# iceWerx_Carrier.net
KiCad netlist of a schematic drawn in EAGLE
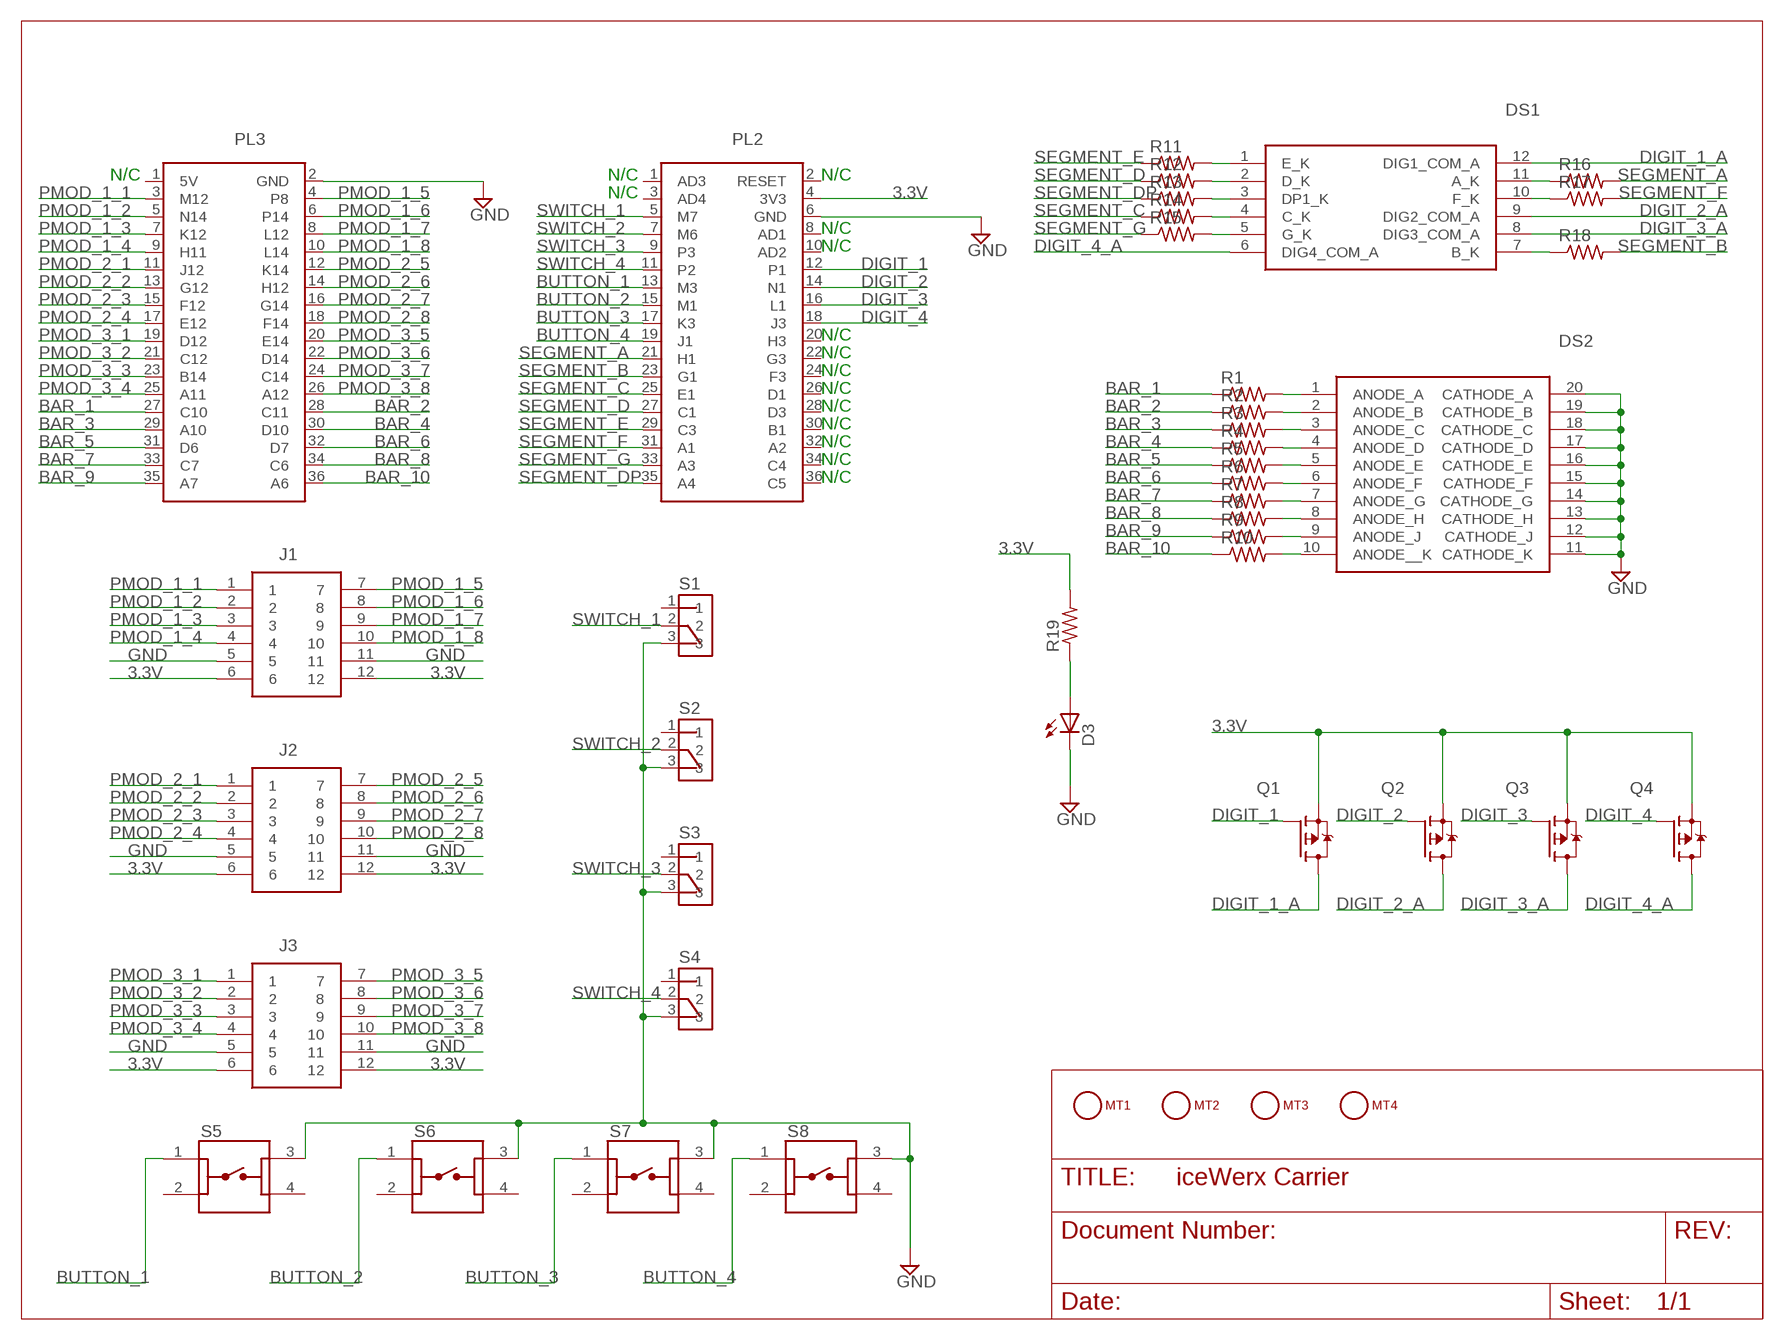
[diagram p0: schematic, sheet 1]

(export (version "E")
  (design (tool "Eeschema 10.0.6"))
  (components
    (comp (ref "D3")
      (value "LED5MM")
      (footprint "eagle-import:LED5MM")
      (libsource (lib "eagle-import") (part "LED5MM"))
    )
    (comp (ref "DS1")
      (value "LDQ-M282RI")
      (footprint "eagle-import:LDQM282RI")
      (fields (field (name "MOUSER_PART_NUMBER") "696-LDQ-M282RI"))
      (libsource (lib "eagle-import") (part "LDQ-M282RI"))
    )
    (comp (ref "DS2")
      (value "LTA-1000G")
      (footprint "eagle-import:DIPS762W50P254L2527H825Q20N")
      (fields (field (name "MOUSER_PART_NUMBER") "859-LTA-1000G"))
      (libsource (lib "eagle-import") (part "LTA-1000G"))
    )
    (comp (ref "J1")
      (value "PMOD-SOCKET-FOR-HOST-BOARD")
      (footprint "eagle-import:PMOD-SOCKET-FOR-HOST-BOARD")
      (libsource (lib "eagle-import") (part "PMOD-SOCKET-FOR-HOST-BOARD"))
    )
    (comp (ref "J2")
      (value "PMOD-SOCKET-FOR-HOST-BOARD")
      (footprint "eagle-import:PMOD-SOCKET-FOR-HOST-BOARD")
      (libsource (lib "eagle-import") (part "PMOD-SOCKET-FOR-HOST-BOARD"))
    )
    (comp (ref "J3")
      (value "PMOD-SOCKET-FOR-HOST-BOARD")
      (footprint "eagle-import:PMOD-SOCKET-FOR-HOST-BOARD")
      (libsource (lib "eagle-import") (part "PMOD-SOCKET-FOR-HOST-BOARD"))
    )
    (comp (ref "MT1")
      (value "MOUNTING_HOLE-125_250_ROUND")
      (footprint "eagle-import:MT_125_250")
      (libsource (lib "eagle-import") (part "MOUNTING_HOLE-125_250_ROUND"))
    )
    (comp (ref "MT2")
      (value "MOUNTING_HOLE-125_250_ROUND")
      (footprint "eagle-import:MT_125_250")
      (libsource (lib "eagle-import") (part "MOUNTING_HOLE-125_250_ROUND"))
    )
    (comp (ref "MT3")
      (value "MOUNTING_HOLE-125_250_ROUND")
      (footprint "eagle-import:MT_125_250")
      (libsource (lib "eagle-import") (part "MOUNTING_HOLE-125_250_ROUND"))
    )
    (comp (ref "MT4")
      (value "MOUNTING_HOLE-125_250_ROUND")
      (footprint "eagle-import:MT_125_250")
      (libsource (lib "eagle-import") (part "MOUNTING_HOLE-125_250_ROUND"))
    )
    (comp (ref "PL2")
      (value "ICEWERX-PL2")
      (footprint "eagle-import:TE_4-1734506-1")
      (libsource (lib "eagle-import") (part "ICEWERX-PL2"))
    )
    (comp (ref "PL3")
      (value "ICEWERX-PL3")
      (footprint "eagle-import:TE_4-1734506-1")
      (libsource (lib "eagle-import") (part "ICEWERX-PL3"))
    )
    (comp (ref "Q1")
      (value "NX2301P")
      (footprint "eagle-import:SOT95P230X110-3N")
      (fields (field (name "MANUFACTURER") "Nexperia"))
      (libsource (lib "eagle-import") (part "NX2301P"))
    )
    (comp (ref "Q2")
      (value "NX2301P")
      (footprint "eagle-import:SOT95P230X110-3N")
      (fields (field (name "MANUFACTURER") "Nexperia"))
      (libsource (lib "eagle-import") (part "NX2301P"))
    )
    (comp (ref "Q3")
      (value "NX2301P")
      (footprint "eagle-import:SOT95P230X110-3N")
      (fields (field (name "MANUFACTURER") "Nexperia"))
      (libsource (lib "eagle-import") (part "NX2301P"))
    )
    (comp (ref "Q4")
      (value "NX2301P")
      (footprint "eagle-import:SOT95P230X110-3N")
      (fields (field (name "MANUFACTURER") "Nexperia"))
      (libsource (lib "eagle-import") (part "NX2301P"))
    )
    (comp (ref "R1")
      (value "R-US_0204/5")
      (footprint "eagle-import:0204_5")
      (libsource (lib "eagle-import") (part "R-US_0204/5"))
    )
    (comp (ref "R2")
      (value "R-US_0204/5")
      (footprint "eagle-import:0204_5")
      (libsource (lib "eagle-import") (part "R-US_0204/5"))
    )
    (comp (ref "R3")
      (value "R-US_0204/5")
      (footprint "eagle-import:0204_5")
      (libsource (lib "eagle-import") (part "R-US_0204/5"))
    )
    (comp (ref "R4")
      (value "R-US_0204/5")
      (footprint "eagle-import:0204_5")
      (libsource (lib "eagle-import") (part "R-US_0204/5"))
    )
    (comp (ref "R5")
      (value "R-US_0204/5")
      (footprint "eagle-import:0204_5")
      (libsource (lib "eagle-import") (part "R-US_0204/5"))
    )
    (comp (ref "R6")
      (value "R-US_0204/5")
      (footprint "eagle-import:0204_5")
      (libsource (lib "eagle-import") (part "R-US_0204/5"))
    )
    (comp (ref "R7")
      (value "R-US_0204/5")
      (footprint "eagle-import:0204_5")
      (libsource (lib "eagle-import") (part "R-US_0204/5"))
    )
    (comp (ref "R8")
      (value "R-US_0204/5")
      (footprint "eagle-import:0204_5")
      (libsource (lib "eagle-import") (part "R-US_0204/5"))
    )
    (comp (ref "R9")
      (value "R-US_0204/5")
      (footprint "eagle-import:0204_5")
      (libsource (lib "eagle-import") (part "R-US_0204/5"))
    )
    (comp (ref "R10")
      (value "R-US_0204/5")
      (footprint "eagle-import:0204_5")
      (libsource (lib "eagle-import") (part "R-US_0204/5"))
    )
    (comp (ref "R11")
      (value "R-US_0204/5")
      (footprint "eagle-import:0204_5")
      (libsource (lib "eagle-import") (part "R-US_0204/5"))
    )
    (comp (ref "R12")
      (value "R-US_0204/5")
      (footprint "eagle-import:0204_5")
      (libsource (lib "eagle-import") (part "R-US_0204/5"))
    )
    (comp (ref "R13")
      (value "R-US_0204/5")
      (footprint "eagle-import:0204_5")
      (libsource (lib "eagle-import") (part "R-US_0204/5"))
    )
    (comp (ref "R14")
      (value "R-US_0204/5")
      (footprint "eagle-import:0204_5")
      (libsource (lib "eagle-import") (part "R-US_0204/5"))
    )
    (comp (ref "R15")
      (value "R-US_0204/5")
      (footprint "eagle-import:0204_5")
      (libsource (lib "eagle-import") (part "R-US_0204/5"))
    )
    (comp (ref "R16")
      (value "R-US_0204/5")
      (footprint "eagle-import:0204_5")
      (libsource (lib "eagle-import") (part "R-US_0204/5"))
    )
    (comp (ref "R17")
      (value "R-US_0204/5")
      (footprint "eagle-import:0204_5")
      (libsource (lib "eagle-import") (part "R-US_0204/5"))
    )
    (comp (ref "R18")
      (value "R-US_0204/5")
      (footprint "eagle-import:0204_5")
      (libsource (lib "eagle-import") (part "R-US_0204/5"))
    )
    (comp (ref "R19")
      (value "R-US_0204/5")
      (footprint "eagle-import:0204_5")
      (libsource (lib "eagle-import") (part "R-US_0204/5"))
    )
    (comp (ref "S1")
      (value "OS102011MS2QN1")
      (footprint "eagle-import:SW_OS102011MS2QN1")
      (fields (field (name "MANUFACTURER") "C&K"))
      (libsource (lib "eagle-import") (part "OS102011MS2QN1"))
    )
    (comp (ref "S2")
      (value "OS102011MS2QN1")
      (footprint "eagle-import:SW_OS102011MS2QN1")
      (fields (field (name "MANUFACTURER") "C&K"))
      (libsource (lib "eagle-import") (part "OS102011MS2QN1"))
    )
    (comp (ref "S3")
      (value "OS102011MS2QN1")
      (footprint "eagle-import:SW_OS102011MS2QN1")
      (fields (field (name "MANUFACTURER") "C&K"))
      (libsource (lib "eagle-import") (part "OS102011MS2QN1"))
    )
    (comp (ref "S4")
      (value "OS102011MS2QN1")
      (footprint "eagle-import:SW_OS102011MS2QN1")
      (fields (field (name "MANUFACTURER") "C&K"))
      (libsource (lib "eagle-import") (part "OS102011MS2QN1"))
    )
    (comp (ref "S5")
      (value "1825910-7")
      (footprint "eagle-import:SW_1825910-7")
      (fields (field (name "MANUFACTURER") "TE Connectivity"))
      (libsource (lib "eagle-import") (part "1825910-7"))
    )
    (comp (ref "S6")
      (value "1825910-7")
      (footprint "eagle-import:SW_1825910-7")
      (fields (field (name "MANUFACTURER") "TE Connectivity"))
      (libsource (lib "eagle-import") (part "1825910-7"))
    )
    (comp (ref "S7")
      (value "1825910-7")
      (footprint "eagle-import:SW_1825910-7")
      (fields (field (name "MANUFACTURER") "TE Connectivity"))
      (libsource (lib "eagle-import") (part "1825910-7"))
    )
    (comp (ref "S8")
      (value "1825910-7")
      (footprint "eagle-import:SW_1825910-7")
      (fields (field (name "MANUFACTURER") "TE Connectivity"))
      (libsource (lib "eagle-import") (part "1825910-7"))
    )
  )
  (nets
    (net (code "1") (name "/3.3V") (class "Default")
      (node (ref "J1") (pin "12") (pinfunction "12_12") (pintype "bidirectional"))
      (node (ref "J1") (pin "6") (pinfunction "6_6") (pintype "bidirectional"))
      (node (ref "J2") (pin "12") (pinfunction "12_12") (pintype "bidirectional"))
      (node (ref "J2") (pin "6") (pinfunction "6_6") (pintype "bidirectional"))
      (node (ref "J3") (pin "12") (pinfunction "12_12") (pintype "bidirectional"))
      (node (ref "J3") (pin "6") (pinfunction "6_6") (pintype "bidirectional"))
      (node (ref "PL2") (pin "4") (pinfunction "3V3_4") (pintype "bidirectional"))
      (node (ref "Q1") (pin "2") (pinfunction "S_2") (pintype "passive"))
      (node (ref "Q2") (pin "2") (pinfunction "S_2") (pintype "passive"))
      (node (ref "Q3") (pin "2") (pinfunction "S_2") (pintype "passive"))
      (node (ref "Q4") (pin "2") (pinfunction "S_2") (pintype "passive"))
      (node (ref "R19") (pin "2") (pinfunction "2_2") (pintype "passive"))
    )
    (net (code "2") (name "/BAR_1") (class "Default")
      (node (ref "PL3") (pin "27") (pinfunction "C10_27") (pintype "bidirectional"))
      (node (ref "R1") (pin "1") (pinfunction "1_1") (pintype "passive"))
    )
    (net (code "3") (name "/BAR_2") (class "Default")
      (node (ref "PL3") (pin "28") (pinfunction "C11_28") (pintype "bidirectional"))
      (node (ref "R2") (pin "1") (pinfunction "1_1") (pintype "passive"))
    )
    (net (code "4") (name "/BAR_3") (class "Default")
      (node (ref "PL3") (pin "29") (pinfunction "A10_29") (pintype "bidirectional"))
      (node (ref "R3") (pin "1") (pinfunction "1_1") (pintype "passive"))
    )
    (net (code "5") (name "/BAR_4") (class "Default")
      (node (ref "PL3") (pin "30") (pinfunction "D10_30") (pintype "bidirectional"))
      (node (ref "R4") (pin "1") (pinfunction "1_1") (pintype "passive"))
    )
    (net (code "6") (name "/BAR_5") (class "Default")
      (node (ref "PL3") (pin "31") (pinfunction "D6_31") (pintype "bidirectional"))
      (node (ref "R5") (pin "1") (pinfunction "1_1") (pintype "passive"))
    )
    (net (code "7") (name "/BAR_6") (class "Default")
      (node (ref "PL3") (pin "32") (pinfunction "D7_32") (pintype "bidirectional"))
      (node (ref "R6") (pin "1") (pinfunction "1_1") (pintype "passive"))
    )
    (net (code "8") (name "/BAR_7") (class "Default")
      (node (ref "PL3") (pin "33") (pinfunction "C7_33") (pintype "bidirectional"))
      (node (ref "R7") (pin "1") (pinfunction "1_1") (pintype "passive"))
    )
    (net (code "9") (name "/BAR_8") (class "Default")
      (node (ref "PL3") (pin "34") (pinfunction "C6_34") (pintype "bidirectional"))
      (node (ref "R8") (pin "1") (pinfunction "1_1") (pintype "passive"))
    )
    (net (code "10") (name "/BAR_9") (class "Default")
      (node (ref "PL3") (pin "35") (pinfunction "A7_35") (pintype "bidirectional"))
      (node (ref "R9") (pin "1") (pinfunction "1_1") (pintype "passive"))
    )
    (net (code "11") (name "/BAR_10") (class "Default")
      (node (ref "PL3") (pin "36") (pinfunction "A6_36") (pintype "bidirectional"))
      (node (ref "R10") (pin "1") (pinfunction "1_1") (pintype "passive"))
    )
    (net (code "12") (name "/BUTTON_1") (class "Default")
      (node (ref "PL2") (pin "13") (pinfunction "M3_13") (pintype "bidirectional"))
      (node (ref "S5") (pin "1") (pinfunction "1_1") (pintype "passive"))
    )
    (net (code "13") (name "/BUTTON_2") (class "Default")
      (node (ref "PL2") (pin "15") (pinfunction "M1_15") (pintype "bidirectional"))
      (node (ref "S6") (pin "1") (pinfunction "1_1") (pintype "passive"))
    )
    (net (code "14") (name "/BUTTON_3") (class "Default")
      (node (ref "PL2") (pin "17") (pinfunction "K3_17") (pintype "bidirectional"))
      (node (ref "S7") (pin "1") (pinfunction "1_1") (pintype "passive"))
    )
    (net (code "15") (name "/BUTTON_4") (class "Default")
      (node (ref "PL2") (pin "19") (pinfunction "J1_19") (pintype "bidirectional"))
      (node (ref "S8") (pin "1") (pinfunction "1_1") (pintype "passive"))
    )
    (net (code "16") (name "/DIGIT_1") (class "Default")
      (node (ref "PL2") (pin "12") (pinfunction "P1_12") (pintype "bidirectional"))
      (node (ref "Q1") (pin "1") (pinfunction "G_1") (pintype "passive"))
    )
    (net (code "17") (name "/DIGIT_1_A") (class "Default")
      (node (ref "DS1") (pin "12") (pinfunction "DIG1_COM_A_12") (pintype "bidirectional"))
      (node (ref "Q1") (pin "3") (pinfunction "D_3") (pintype "passive"))
    )
    (net (code "18") (name "/DIGIT_2") (class "Default")
      (node (ref "PL2") (pin "14") (pinfunction "N1_14") (pintype "bidirectional"))
      (node (ref "Q2") (pin "1") (pinfunction "G_1") (pintype "passive"))
    )
    (net (code "19") (name "/DIGIT_2_A") (class "Default")
      (node (ref "DS1") (pin "9") (pinfunction "DIG2_COM_A_9") (pintype "bidirectional"))
      (node (ref "Q2") (pin "3") (pinfunction "D_3") (pintype "passive"))
    )
    (net (code "20") (name "/DIGIT_3") (class "Default")
      (node (ref "PL2") (pin "16") (pinfunction "L1_16") (pintype "bidirectional"))
      (node (ref "Q3") (pin "1") (pinfunction "G_1") (pintype "passive"))
    )
    (net (code "21") (name "/DIGIT_3_A") (class "Default")
      (node (ref "DS1") (pin "8") (pinfunction "DIG3_COM_A_8") (pintype "bidirectional"))
      (node (ref "Q3") (pin "3") (pinfunction "D_3") (pintype "passive"))
    )
    (net (code "22") (name "/DIGIT_4") (class "Default")
      (node (ref "PL2") (pin "18") (pinfunction "J3_18") (pintype "bidirectional"))
      (node (ref "Q4") (pin "1") (pinfunction "G_1") (pintype "passive"))
    )
    (net (code "23") (name "/DIGIT_4_A") (class "Default")
      (node (ref "DS1") (pin "6") (pinfunction "DIG4_COM_A_6") (pintype "bidirectional"))
      (node (ref "Q4") (pin "3") (pinfunction "D_3") (pintype "passive"))
    )
    (net (code "24") (name "/PMOD_1_1") (class "Default")
      (node (ref "J1") (pin "1") (pinfunction "1_1") (pintype "bidirectional"))
      (node (ref "PL3") (pin "3") (pinfunction "M12_3") (pintype "bidirectional"))
    )
    (net (code "25") (name "/PMOD_1_2") (class "Default")
      (node (ref "J1") (pin "2") (pinfunction "2_2") (pintype "bidirectional"))
      (node (ref "PL3") (pin "5") (pinfunction "N14_5") (pintype "bidirectional"))
    )
    (net (code "26") (name "/PMOD_1_3") (class "Default")
      (node (ref "J1") (pin "3") (pinfunction "3_3") (pintype "bidirectional"))
      (node (ref "PL3") (pin "7") (pinfunction "K12_7") (pintype "bidirectional"))
    )
    (net (code "27") (name "/PMOD_1_4") (class "Default")
      (node (ref "J1") (pin "4") (pinfunction "4_4") (pintype "bidirectional"))
      (node (ref "PL3") (pin "9") (pinfunction "H11_9") (pintype "bidirectional"))
    )
    (net (code "28") (name "/PMOD_1_5") (class "Default")
      (node (ref "J1") (pin "7") (pinfunction "7_7") (pintype "bidirectional"))
      (node (ref "PL3") (pin "4") (pinfunction "P8_4") (pintype "bidirectional"))
    )
    (net (code "29") (name "/PMOD_1_6") (class "Default")
      (node (ref "J1") (pin "8") (pinfunction "8_8") (pintype "bidirectional"))
      (node (ref "PL3") (pin "6") (pinfunction "P14_6") (pintype "bidirectional"))
    )
    (net (code "30") (name "/PMOD_1_7") (class "Default")
      (node (ref "J1") (pin "9") (pinfunction "9_9") (pintype "bidirectional"))
      (node (ref "PL3") (pin "8") (pinfunction "L12_8") (pintype "bidirectional"))
    )
    (net (code "31") (name "/PMOD_1_8") (class "Default")
      (node (ref "J1") (pin "10") (pinfunction "10_10") (pintype "bidirectional"))
      (node (ref "PL3") (pin "10") (pinfunction "L14_10") (pintype "bidirectional"))
    )
    (net (code "32") (name "/PMOD_2_1") (class "Default")
      (node (ref "J2") (pin "1") (pinfunction "1_1") (pintype "bidirectional"))
      (node (ref "PL3") (pin "11") (pinfunction "J12_11") (pintype "bidirectional"))
    )
    (net (code "33") (name "/PMOD_2_2") (class "Default")
      (node (ref "J2") (pin "2") (pinfunction "2_2") (pintype "bidirectional"))
      (node (ref "PL3") (pin "13") (pinfunction "G12_13") (pintype "bidirectional"))
    )
    (net (code "34") (name "/PMOD_2_3") (class "Default")
      (node (ref "J2") (pin "3") (pinfunction "3_3") (pintype "bidirectional"))
      (node (ref "PL3") (pin "15") (pinfunction "F12_15") (pintype "bidirectional"))
    )
    (net (code "35") (name "/PMOD_2_4") (class "Default")
      (node (ref "J2") (pin "4") (pinfunction "4_4") (pintype "bidirectional"))
      (node (ref "PL3") (pin "17") (pinfunction "E12_17") (pintype "bidirectional"))
    )
    (net (code "36") (name "/PMOD_2_5") (class "Default")
      (node (ref "J2") (pin "7") (pinfunction "7_7") (pintype "bidirectional"))
      (node (ref "PL3") (pin "12") (pinfunction "K14_12") (pintype "bidirectional"))
    )
    (net (code "37") (name "/PMOD_2_6") (class "Default")
      (node (ref "J2") (pin "8") (pinfunction "8_8") (pintype "bidirectional"))
      (node (ref "PL3") (pin "14") (pinfunction "H12_14") (pintype "bidirectional"))
    )
    (net (code "38") (name "/PMOD_2_7") (class "Default")
      (node (ref "J2") (pin "9") (pinfunction "9_9") (pintype "bidirectional"))
      (node (ref "PL3") (pin "16") (pinfunction "G14_16") (pintype "bidirectional"))
    )
    (net (code "39") (name "/PMOD_2_8") (class "Default")
      (node (ref "J2") (pin "10") (pinfunction "10_10") (pintype "bidirectional"))
      (node (ref "PL3") (pin "18") (pinfunction "F14_18") (pintype "bidirectional"))
    )
    (net (code "40") (name "/PMOD_3_1") (class "Default")
      (node (ref "J3") (pin "1") (pinfunction "1_1") (pintype "bidirectional"))
      (node (ref "PL3") (pin "19") (pinfunction "D12_19") (pintype "bidirectional"))
    )
    (net (code "41") (name "/PMOD_3_2") (class "Default")
      (node (ref "J3") (pin "2") (pinfunction "2_2") (pintype "bidirectional"))
      (node (ref "PL3") (pin "21") (pinfunction "C12_21") (pintype "bidirectional"))
    )
    (net (code "42") (name "/PMOD_3_3") (class "Default")
      (node (ref "J3") (pin "3") (pinfunction "3_3") (pintype "bidirectional"))
      (node (ref "PL3") (pin "23") (pinfunction "B14_23") (pintype "bidirectional"))
    )
    (net (code "43") (name "/PMOD_3_4") (class "Default")
      (node (ref "J3") (pin "4") (pinfunction "4_4") (pintype "bidirectional"))
      (node (ref "PL3") (pin "25") (pinfunction "A11_25") (pintype "bidirectional"))
    )
    (net (code "44") (name "/PMOD_3_5") (class "Default")
      (node (ref "J3") (pin "7") (pinfunction "7_7") (pintype "bidirectional"))
      (node (ref "PL3") (pin "20") (pinfunction "E14_20") (pintype "bidirectional"))
    )
    (net (code "45") (name "/PMOD_3_6") (class "Default")
      (node (ref "J3") (pin "8") (pinfunction "8_8") (pintype "bidirectional"))
      (node (ref "PL3") (pin "22") (pinfunction "D14_22") (pintype "bidirectional"))
    )
    (net (code "46") (name "/PMOD_3_7") (class "Default")
      (node (ref "J3") (pin "9") (pinfunction "9_9") (pintype "bidirectional"))
      (node (ref "PL3") (pin "24") (pinfunction "C14_24") (pintype "bidirectional"))
    )
    (net (code "47") (name "/PMOD_3_8") (class "Default")
      (node (ref "J3") (pin "10") (pinfunction "10_10") (pintype "bidirectional"))
      (node (ref "PL3") (pin "26") (pinfunction "A12_26") (pintype "bidirectional"))
    )
    (net (code "48") (name "/SEGMENT_A") (class "Default")
      (node (ref "PL2") (pin "21") (pinfunction "H1_21") (pintype "bidirectional"))
      (node (ref "R16") (pin "2") (pinfunction "2_2") (pintype "passive"))
    )
    (net (code "49") (name "/SEGMENT_B") (class "Default")
      (node (ref "PL2") (pin "23") (pinfunction "G1_23") (pintype "bidirectional"))
      (node (ref "R18") (pin "2") (pinfunction "2_2") (pintype "passive"))
    )
    (net (code "50") (name "/SEGMENT_C") (class "Default")
      (node (ref "PL2") (pin "25") (pinfunction "E1_25") (pintype "bidirectional"))
      (node (ref "R14") (pin "1") (pinfunction "1_1") (pintype "passive"))
    )
    (net (code "51") (name "/SEGMENT_D") (class "Default")
      (node (ref "PL2") (pin "27") (pinfunction "C1_27") (pintype "bidirectional"))
      (node (ref "R12") (pin "1") (pinfunction "1_1") (pintype "passive"))
    )
    (net (code "52") (name "/SEGMENT_DP") (class "Default")
      (node (ref "PL2") (pin "35") (pinfunction "A4_35") (pintype "bidirectional"))
      (node (ref "R13") (pin "1") (pinfunction "1_1") (pintype "passive"))
    )
    (net (code "53") (name "/SEGMENT_E") (class "Default")
      (node (ref "PL2") (pin "29") (pinfunction "C3_29") (pintype "bidirectional"))
      (node (ref "R11") (pin "1") (pinfunction "1_1") (pintype "passive"))
    )
    (net (code "54") (name "/SEGMENT_F") (class "Default")
      (node (ref "PL2") (pin "31") (pinfunction "A1_31") (pintype "bidirectional"))
      (node (ref "R17") (pin "2") (pinfunction "2_2") (pintype "passive"))
    )
    (net (code "55") (name "/SEGMENT_G") (class "Default")
      (node (ref "PL2") (pin "33") (pinfunction "A3_33") (pintype "bidirectional"))
      (node (ref "R15") (pin "1") (pinfunction "1_1") (pintype "passive"))
    )
    (net (code "56") (name "/SWITCH_1") (class "Default")
      (node (ref "PL2") (pin "5") (pinfunction "M7_5") (pintype "bidirectional"))
      (node (ref "S1") (pin "2") (pinfunction "2_2") (pintype "passive"))
    )
    (net (code "57") (name "/SWITCH_2") (class "Default")
      (node (ref "PL2") (pin "7") (pinfunction "M6_7") (pintype "bidirectional"))
      (node (ref "S2") (pin "2") (pinfunction "2_2") (pintype "passive"))
    )
    (net (code "58") (name "/SWITCH_3") (class "Default")
      (node (ref "PL2") (pin "9") (pinfunction "P3_9") (pintype "bidirectional"))
      (node (ref "S3") (pin "2") (pinfunction "2_2") (pintype "passive"))
    )
    (net (code "59") (name "/SWITCH_4") (class "Default")
      (node (ref "PL2") (pin "11") (pinfunction "P2_11") (pintype "bidirectional"))
      (node (ref "S4") (pin "2") (pinfunction "2_2") (pintype "passive"))
    )
    (net (code "60") (name "GND") (class "Default")
      (node (ref "D3") (pin "K") (pinfunction "C_K") (pintype "passive"))
      (node (ref "DS2") (pin "11") (pinfunction "CATHODE_K_11") (pintype "bidirectional"))
      (node (ref "DS2") (pin "12") (pinfunction "CATHODE_J_12") (pintype "bidirectional"))
      (node (ref "DS2") (pin "13") (pinfunction "CATHODE_H_13") (pintype "bidirectional"))
      (node (ref "DS2") (pin "14") (pinfunction "CATHODE_G_14") (pintype "bidirectional"))
      (node (ref "DS2") (pin "15") (pinfunction "CATHODE_F_15") (pintype "bidirectional"))
      (node (ref "DS2") (pin "16") (pinfunction "CATHODE_E_16") (pintype "bidirectional"))
      (node (ref "DS2") (pin "17") (pinfunction "CATHODE_D_17") (pintype "bidirectional"))
      (node (ref "DS2") (pin "18") (pinfunction "CATHODE_C_18") (pintype "bidirectional"))
      (node (ref "DS2") (pin "19") (pinfunction "CATHODE_B_19") (pintype "bidirectional"))
      (node (ref "DS2") (pin "20") (pinfunction "CATHODE_A_20") (pintype "bidirectional"))
      (node (ref "J1") (pin "11") (pinfunction "11_11") (pintype "bidirectional"))
      (node (ref "J1") (pin "5") (pinfunction "5_5") (pintype "bidirectional"))
      (node (ref "J2") (pin "11") (pinfunction "11_11") (pintype "bidirectional"))
      (node (ref "J2") (pin "5") (pinfunction "5_5") (pintype "bidirectional"))
      (node (ref "J3") (pin "11") (pinfunction "11_11") (pintype "bidirectional"))
      (node (ref "J3") (pin "5") (pinfunction "5_5") (pintype "bidirectional"))
      (node (ref "PL2") (pin "6") (pinfunction "GND_6") (pintype "bidirectional"))
      (node (ref "PL3") (pin "2") (pinfunction "GND_2") (pintype "bidirectional"))
      (node (ref "S1") (pin "3") (pinfunction "3_3") (pintype "passive"))
      (node (ref "S2") (pin "3") (pinfunction "3_3") (pintype "passive"))
      (node (ref "S3") (pin "3") (pinfunction "3_3") (pintype "passive"))
      (node (ref "S4") (pin "3") (pinfunction "3_3") (pintype "passive"))
      (node (ref "S5") (pin "3") (pinfunction "3_3") (pintype "passive"))
      (node (ref "S6") (pin "3") (pinfunction "3_3") (pintype "passive"))
      (node (ref "S7") (pin "3") (pinfunction "3_3") (pintype "passive"))
      (node (ref "S8") (pin "3") (pinfunction "3_3") (pintype "passive"))
    )
    (net (code "61") (name "Net-(D3-PadA)") (class "Default")
      (node (ref "D3") (pin "A") (pinfunction "A_A") (pintype "passive"))
      (node (ref "R19") (pin "1") (pinfunction "1_1") (pintype "passive"))
    )
    (net (code "62") (name "Net-(DS1-A_K)") (class "Default")
      (node (ref "DS1") (pin "11") (pinfunction "A_K_11") (pintype "bidirectional"))
      (node (ref "R16") (pin "1") (pinfunction "1_1") (pintype "passive"))
    )
    (net (code "63") (name "Net-(DS1-B_K)") (class "Default")
      (node (ref "DS1") (pin "7") (pinfunction "B_K_7") (pintype "bidirectional"))
      (node (ref "R18") (pin "1") (pinfunction "1_1") (pintype "passive"))
    )
    (net (code "64") (name "Net-(DS1-C_K)") (class "Default")
      (node (ref "DS1") (pin "4") (pinfunction "C_K_4") (pintype "bidirectional"))
      (node (ref "R14") (pin "2") (pinfunction "2_2") (pintype "passive"))
    )
    (net (code "65") (name "Net-(DS1-DP1_K)") (class "Default")
      (node (ref "DS1") (pin "3") (pinfunction "DP1_K_3") (pintype "bidirectional"))
      (node (ref "R13") (pin "2") (pinfunction "2_2") (pintype "passive"))
    )
    (net (code "66") (name "Net-(DS1-D_K)") (class "Default")
      (node (ref "DS1") (pin "2") (pinfunction "D_K_2") (pintype "bidirectional"))
      (node (ref "R12") (pin "2") (pinfunction "2_2") (pintype "passive"))
    )
    (net (code "67") (name "Net-(DS1-E_K)") (class "Default")
      (node (ref "DS1") (pin "1") (pinfunction "E_K_1") (pintype "bidirectional"))
      (node (ref "R11") (pin "2") (pinfunction "2_2") (pintype "passive"))
    )
    (net (code "68") (name "Net-(DS1-F_K)") (class "Default")
      (node (ref "DS1") (pin "10") (pinfunction "F_K_10") (pintype "bidirectional"))
      (node (ref "R17") (pin "1") (pinfunction "1_1") (pintype "passive"))
    )
    (net (code "69") (name "Net-(DS1-G_K)") (class "Default")
      (node (ref "DS1") (pin "5") (pinfunction "G_K_5") (pintype "bidirectional"))
      (node (ref "R15") (pin "2") (pinfunction "2_2") (pintype "passive"))
    )
    (net (code "70") (name "Net-(DS2-ANODE_A)") (class "Default")
      (node (ref "DS2") (pin "1") (pinfunction "ANODE_A_1") (pintype "bidirectional"))
      (node (ref "R1") (pin "2") (pinfunction "2_2") (pintype "passive"))
    )
    (net (code "71") (name "Net-(DS2-ANODE_B)") (class "Default")
      (node (ref "DS2") (pin "2") (pinfunction "ANODE_B_2") (pintype "bidirectional"))
      (node (ref "R2") (pin "2") (pinfunction "2_2") (pintype "passive"))
    )
    (net (code "72") (name "Net-(DS2-ANODE_C)") (class "Default")
      (node (ref "DS2") (pin "3") (pinfunction "ANODE_C_3") (pintype "bidirectional"))
      (node (ref "R3") (pin "2") (pinfunction "2_2") (pintype "passive"))
    )
    (net (code "73") (name "Net-(DS2-ANODE_D)") (class "Default")
      (node (ref "DS2") (pin "4") (pinfunction "ANODE_D_4") (pintype "bidirectional"))
      (node (ref "R4") (pin "2") (pinfunction "2_2") (pintype "passive"))
    )
    (net (code "74") (name "Net-(DS2-ANODE_E)") (class "Default")
      (node (ref "DS2") (pin "5") (pinfunction "ANODE_E_5") (pintype "bidirectional"))
      (node (ref "R5") (pin "2") (pinfunction "2_2") (pintype "passive"))
    )
    (net (code "75") (name "Net-(DS2-ANODE_F)") (class "Default")
      (node (ref "DS2") (pin "6") (pinfunction "ANODE_F_6") (pintype "bidirectional"))
      (node (ref "R6") (pin "2") (pinfunction "2_2") (pintype "passive"))
    )
    (net (code "76") (name "Net-(DS2-ANODE_G)") (class "Default")
      (node (ref "DS2") (pin "7") (pinfunction "ANODE_G_7") (pintype "bidirectional"))
      (node (ref "R7") (pin "2") (pinfunction "2_2") (pintype "passive"))
    )
    (net (code "77") (name "Net-(DS2-ANODE_H)") (class "Default")
      (node (ref "DS2") (pin "8") (pinfunction "ANODE_H_8") (pintype "bidirectional"))
      (node (ref "R8") (pin "2") (pinfunction "2_2") (pintype "passive"))
    )
    (net (code "78") (name "Net-(DS2-ANODE_J)") (class "Default")
      (node (ref "DS2") (pin "9") (pinfunction "ANODE_J_9") (pintype "bidirectional"))
      (node (ref "R9") (pin "2") (pinfunction "2_2") (pintype "passive"))
    )
    (net (code "79") (name "Net-(DS2-ANODE__K)") (class "Default")
      (node (ref "DS2") (pin "10") (pinfunction "ANODE__K_10") (pintype "bidirectional"))
      (node (ref "R10") (pin "2") (pinfunction "2_2") (pintype "passive"))
    )
    (net (code "80") (name "unconnected-(MT1-P$1-Pad1)") (class "Default")
      (node (ref "MT1") (pin "1") (pinfunction "P$1_1") (pintype "bidirectional"))
    )
    (net (code "81") (name "unconnected-(MT2-P$1-Pad1)") (class "Default")
      (node (ref "MT2") (pin "1") (pinfunction "P$1_1") (pintype "bidirectional"))
    )
    (net (code "82") (name "unconnected-(MT3-P$1-Pad1)") (class "Default")
      (node (ref "MT3") (pin "1") (pinfunction "P$1_1") (pintype "bidirectional"))
    )
    (net (code "83") (name "unconnected-(MT4-P$1-Pad1)") (class "Default")
      (node (ref "MT4") (pin "1") (pinfunction "P$1_1") (pintype "bidirectional"))
    )
    (net (code "84") (name "unconnected-(PL2-A2-Pad32)") (class "Default")
      (node (ref "PL2") (pin "32") (pinfunction "A2_32") (pintype "bidirectional"))
    )
    (net (code "85") (name "unconnected-(PL2-AD1-Pad8)") (class "Default")
      (node (ref "PL2") (pin "8") (pinfunction "AD1_8") (pintype "bidirectional"))
    )
    (net (code "86") (name "unconnected-(PL2-AD2-Pad10)") (class "Default")
      (node (ref "PL2") (pin "10") (pinfunction "AD2_10") (pintype "bidirectional"))
    )
    (net (code "87") (name "unconnected-(PL2-AD3-Pad1)") (class "Default")
      (node (ref "PL2") (pin "1") (pinfunction "AD3_1") (pintype "bidirectional"))
    )
    (net (code "88") (name "unconnected-(PL2-AD4-Pad3)") (class "Default")
      (node (ref "PL2") (pin "3") (pinfunction "AD4_3") (pintype "bidirectional"))
    )
    (net (code "89") (name "unconnected-(PL2-B1-Pad30)") (class "Default")
      (node (ref "PL2") (pin "30") (pinfunction "B1_30") (pintype "bidirectional"))
    )
    (net (code "90") (name "unconnected-(PL2-C4-Pad34)") (class "Default")
      (node (ref "PL2") (pin "34") (pinfunction "C4_34") (pintype "bidirectional"))
    )
    (net (code "91") (name "unconnected-(PL2-C5-Pad36)") (class "Default")
      (node (ref "PL2") (pin "36") (pinfunction "C5_36") (pintype "bidirectional"))
    )
    (net (code "92") (name "unconnected-(PL2-D1-Pad26)") (class "Default")
      (node (ref "PL2") (pin "26") (pinfunction "D1_26") (pintype "bidirectional"))
    )
    (net (code "93") (name "unconnected-(PL2-D3-Pad28)") (class "Default")
      (node (ref "PL2") (pin "28") (pinfunction "D3_28") (pintype "bidirectional"))
    )
    (net (code "94") (name "unconnected-(PL2-F3-Pad24)") (class "Default")
      (node (ref "PL2") (pin "24") (pinfunction "F3_24") (pintype "bidirectional"))
    )
    (net (code "95") (name "unconnected-(PL2-G3-Pad22)") (class "Default")
      (node (ref "PL2") (pin "22") (pinfunction "G3_22") (pintype "bidirectional"))
    )
    (net (code "96") (name "unconnected-(PL2-H3-Pad20)") (class "Default")
      (node (ref "PL2") (pin "20") (pinfunction "H3_20") (pintype "bidirectional"))
    )
    (net (code "97") (name "unconnected-(PL2-RESET-Pad2)") (class "Default")
      (node (ref "PL2") (pin "2") (pinfunction "RESET_2") (pintype "bidirectional"))
    )
    (net (code "98") (name "unconnected-(PL3-5V-Pad1)") (class "Default")
      (node (ref "PL3") (pin "1") (pinfunction "5V_1") (pintype "bidirectional"))
    )
    (net (code "99") (name "unconnected-(S1-Pad1)") (class "Default")
      (node (ref "S1") (pin "1") (pinfunction "1_1") (pintype "passive"))
    )
    (net (code "100") (name "unconnected-(S2-Pad1)") (class "Default")
      (node (ref "S2") (pin "1") (pinfunction "1_1") (pintype "passive"))
    )
    (net (code "101") (name "unconnected-(S3-Pad1)") (class "Default")
      (node (ref "S3") (pin "1") (pinfunction "1_1") (pintype "passive"))
    )
    (net (code "102") (name "unconnected-(S4-Pad1)") (class "Default")
      (node (ref "S4") (pin "1") (pinfunction "1_1") (pintype "passive"))
    )
    (net (code "103") (name "unconnected-(S5-Pad2)") (class "Default")
      (node (ref "S5") (pin "2") (pinfunction "2_2") (pintype "passive"))
    )
    (net (code "104") (name "unconnected-(S5-Pad4)") (class "Default")
      (node (ref "S5") (pin "4") (pinfunction "4_4") (pintype "passive"))
    )
    (net (code "105") (name "unconnected-(S6-Pad2)") (class "Default")
      (node (ref "S6") (pin "2") (pinfunction "2_2") (pintype "passive"))
    )
    (net (code "106") (name "unconnected-(S6-Pad4)") (class "Default")
      (node (ref "S6") (pin "4") (pinfunction "4_4") (pintype "passive"))
    )
    (net (code "107") (name "unconnected-(S7-Pad2)") (class "Default")
      (node (ref "S7") (pin "2") (pinfunction "2_2") (pintype "passive"))
    )
    (net (code "108") (name "unconnected-(S7-Pad4)") (class "Default")
      (node (ref "S7") (pin "4") (pinfunction "4_4") (pintype "passive"))
    )
    (net (code "109") (name "unconnected-(S8-Pad2)") (class "Default")
      (node (ref "S8") (pin "2") (pinfunction "2_2") (pintype "passive"))
    )
    (net (code "110") (name "unconnected-(S8-Pad4)") (class "Default")
      (node (ref "S8") (pin "4") (pinfunction "4_4") (pintype "passive"))
    )
  )
)
